# clock_src2.net
KiCad netlist of a schematic drawn in EAGLE
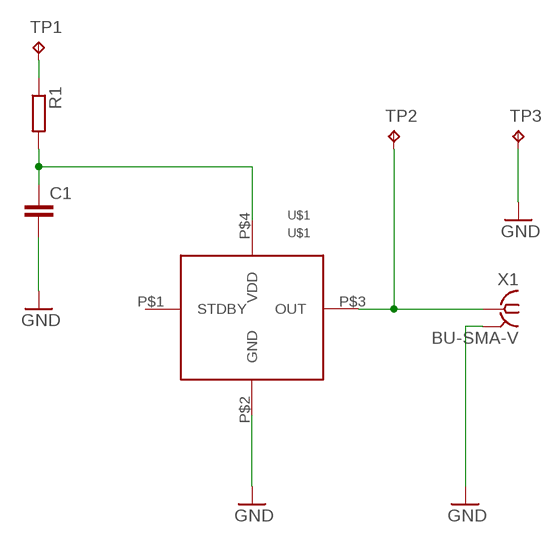
[diagram p0: schematic, sheet 1]

(export (version "E")
  (design (tool "Eeschema 10.0.6"))
  (components
    (comp (ref "C1")
      (value "C-EUC0603")
      (footprint "eagle-import:C0603")
      (libsource (lib "eagle-import") (part "C-EUC0603"))
    )
    (comp (ref "R1")
      (value "R-EU_R0603")
      (footprint "eagle-import:R0603")
      (libsource (lib "eagle-import") (part "R-EU_R0603"))
    )
    (comp (ref "TP1")
      (value "TPTP20SQ")
      (footprint "eagle-import:TP20SQ")
      (libsource (lib "eagle-import") (part "TPTP20SQ"))
    )
    (comp (ref "TP2")
      (value "TPTP20SQ")
      (footprint "eagle-import:TP20SQ")
      (libsource (lib "eagle-import") (part "TPTP20SQ"))
    )
    (comp (ref "TP3")
      (value "TPTP20SQ")
      (footprint "eagle-import:TP20SQ")
      (libsource (lib "eagle-import") (part "TPTP20SQ"))
    )
    (comp (ref "U$1")
      (value "ASFLMB-24525")
      (footprint "eagle-import:ASFLMB-24525")
      (libsource (lib "eagle-import") (part "ASFLMB-24525"))
    )
    (comp (ref "X1")
      (value "BU-SMA-V")
      (footprint "eagle-import:BU-SMA-V")
      (libsource (lib "eagle-import") (part "BU-SMA-V"))
    )
  )
  (nets
    (net (code "1") (name "GND") (class "Default")
      (node (ref "C1") (pin "2") (pinfunction "2_2") (pintype "passive"))
      (node (ref "TP3") (pin "TP") (pinfunction "TP_TP") (pintype "input"))
      (node (ref "U$1") (pin "P$2") (pinfunction "GND_P$2") (pintype "bidirectional"))
      (node (ref "X1") (pin "2") (pinfunction "2_2") (pintype "passive"))
      (node (ref "X1") (pin "3") (pinfunction "2_3") (pintype "passive"))
      (node (ref "X1") (pin "4") (pinfunction "2_4") (pintype "passive"))
      (node (ref "X1") (pin "5") (pinfunction "2_5") (pintype "passive"))
    )
    (net (code "2") (name "Net-(R1-Pad1)") (class "Default")
      (node (ref "R1") (pin "1") (pinfunction "1_1") (pintype "passive"))
      (node (ref "TP1") (pin "TP") (pinfunction "TP_TP") (pintype "input"))
    )
    (net (code "3") (name "Net-(U$1-OUT)") (class "Default")
      (node (ref "TP2") (pin "TP") (pinfunction "TP_TP") (pintype "input"))
      (node (ref "U$1") (pin "P$3") (pinfunction "OUT_P$3") (pintype "bidirectional"))
      (node (ref "X1") (pin "1") (pinfunction "1_1") (pintype "passive"))
    )
    (net (code "4") (name "Net-(U$1-VDD)") (class "Default")
      (node (ref "C1") (pin "1") (pinfunction "1_1") (pintype "passive"))
      (node (ref "R1") (pin "2") (pinfunction "2_2") (pintype "passive"))
      (node (ref "U$1") (pin "P$4") (pinfunction "VDD_P$4") (pintype "bidirectional"))
    )
    (net (code "5") (name "unconnected-(U$1-STDBY-PadP$1)") (class "Default")
      (node (ref "U$1") (pin "P$1") (pinfunction "STDBY_P$1") (pintype "bidirectional"))
    )
  )
)
